# button_brightness_esp32.net
KiCad netlist of a schematic drawn in Altium Designer
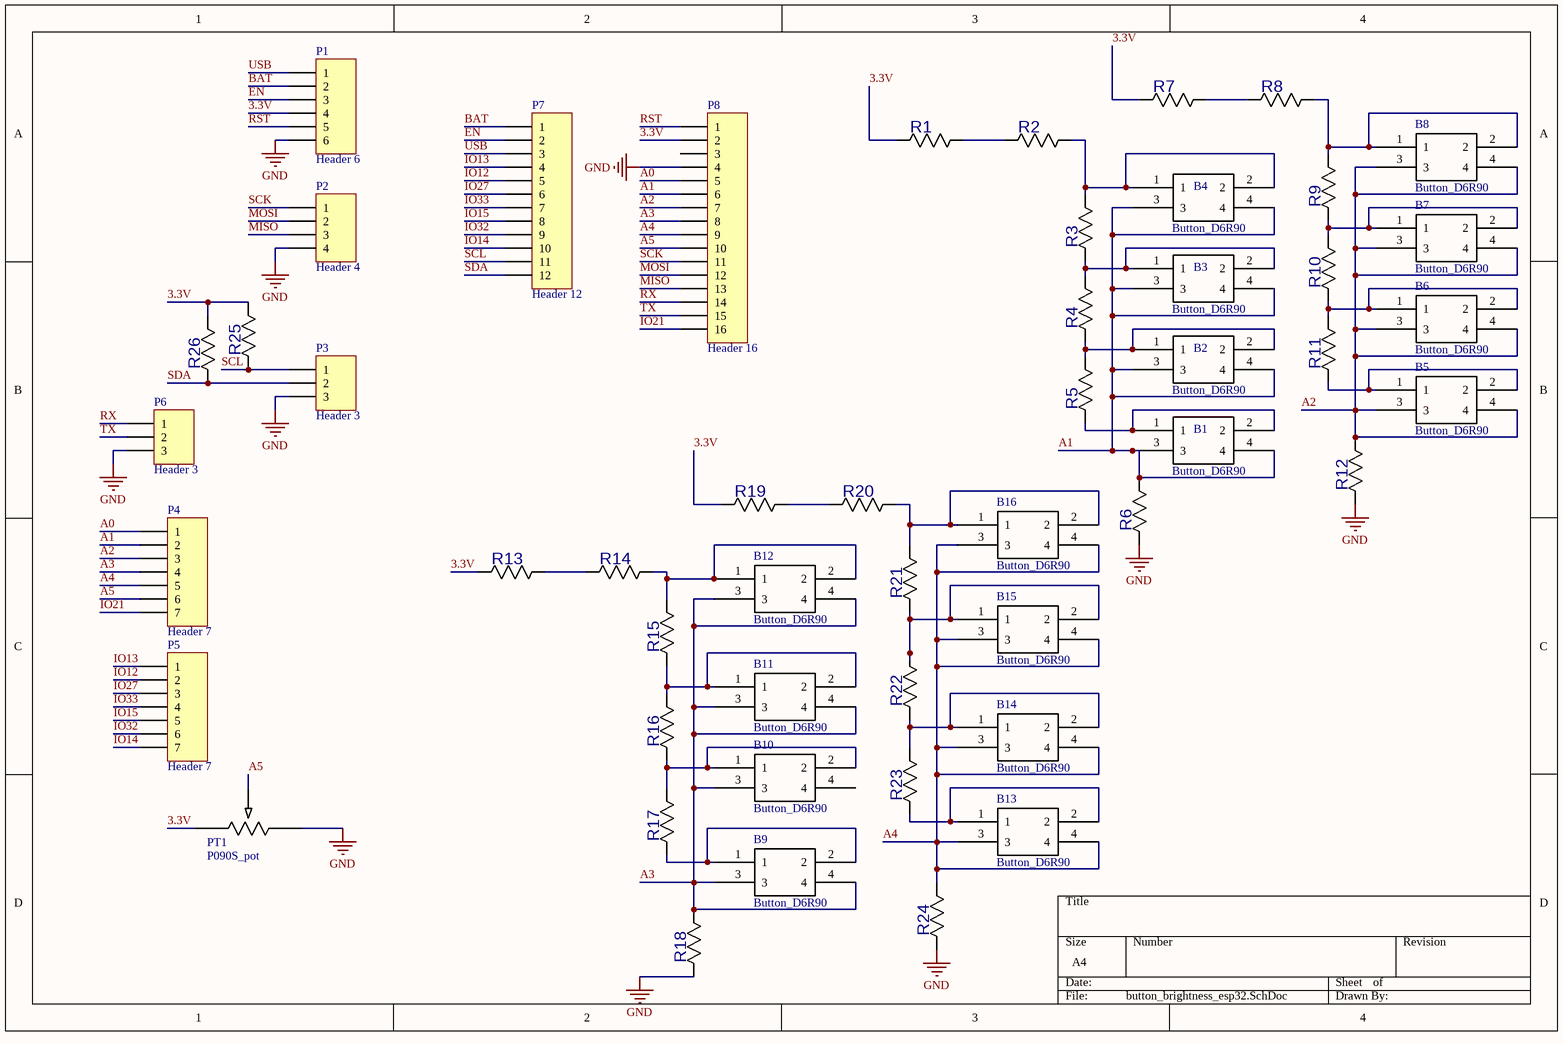
[diagram p0: button_brightness_esp32.SchDoc]

(export (version "E")
  (design (tool "Eeschema 10.0.6"))
  (components
    (comp (ref "B1")
      (value "Button_D6R90")
      (footprint "Button_D6R90")
      (libsource (lib "shematic_lib") (part "Button_D6R90"))
    )
    (comp (ref "B2")
      (value "Button_D6R90")
      (footprint "Button_D6R90")
      (libsource (lib "shematic_lib") (part "Button_D6R90"))
    )
    (comp (ref "B3")
      (value "Button_D6R90")
      (footprint "Button_D6R90")
      (libsource (lib "shematic_lib") (part "Button_D6R90"))
    )
    (comp (ref "B4")
      (value "Button_D6R90")
      (footprint "Button_D6R90")
      (libsource (lib "shematic_lib") (part "Button_D6R90"))
    )
    (comp (ref "B5")
      (value "Button_D6R90")
      (footprint "Button_D6R90")
      (libsource (lib "shematic_lib") (part "Button_D6R90"))
    )
    (comp (ref "B6")
      (value "Button_D6R90")
      (footprint "Button_D6R90")
      (libsource (lib "shematic_lib") (part "Button_D6R90"))
    )
    (comp (ref "B7")
      (value "Button_D6R90")
      (footprint "Button_D6R90")
      (libsource (lib "shematic_lib") (part "Button_D6R90"))
    )
    (comp (ref "B8")
      (value "Button_D6R90")
      (footprint "Button_D6R90")
      (libsource (lib "shematic_lib") (part "Button_D6R90"))
    )
    (comp (ref "B9")
      (value "Button_D6R90")
      (footprint "Button_D6R90")
      (libsource (lib "shematic_lib") (part "Button_D6R90"))
    )
    (comp (ref "B10")
      (value "Button_D6R90")
      (footprint "Button_D6R90")
      (libsource (lib "shematic_lib") (part "Button_D6R90"))
    )
    (comp (ref "B11")
      (value "Button_D6R90")
      (footprint "Button_D6R90")
      (libsource (lib "shematic_lib") (part "Button_D6R90"))
    )
    (comp (ref "B12")
      (value "Button_D6R90")
      (footprint "component_lib:Button_D6R90")
      (libsource (lib "shematic_lib") (part "Button_D6R90"))
    )
    (comp (ref "B13")
      (value "Button_D6R90")
      (footprint "Button_D6R90")
      (libsource (lib "shematic_lib") (part "Button_D6R90"))
    )
    (comp (ref "B14")
      (value "Button_D6R90")
      (footprint "Button_D6R90")
      (libsource (lib "shematic_lib") (part "Button_D6R90"))
    )
    (comp (ref "B15")
      (value "Button_D6R90")
      (footprint "Button_D6R90")
      (libsource (lib "shematic_lib") (part "Button_D6R90"))
    )
    (comp (ref "B16")
      (value "Button_D6R90")
      (footprint "Button_D6R90")
      (libsource (lib "shematic_lib") (part "Button_D6R90"))
    )
    (comp (ref "P1")
      (value "Header 6")
      (footprint "CONN_6")
      (description "Header, 6-Pin")
      (fields (field (name "PUBLISHER") "Altium Limited"))
      (libsource (lib "Miscellaneous Connectors") (part "Header 6"))
    )
    (comp (ref "P2")
      (value "Header 4")
      (footprint "CONN_4")
      (description "Header, 4-Pin")
      (fields (field (name "PUBLISHER") "Altium Limited"))
      (libsource (lib "Miscellaneous Connectors") (part "Header 4"))
    )
    (comp (ref "P3")
      (value "Header 3")
      (footprint "CONN_3")
      (description "Header, 3-Pin")
      (fields (field (name "PUBLISHER") "Altium Limited"))
      (libsource (lib "Miscellaneous Connectors") (part "Header 3"))
    )
    (comp (ref "P4")
      (value "Header 7")
      (footprint "CONN_7")
      (description "Header, 7-Pin")
      (fields (field (name "PUBLISHER") "Altium Limited"))
      (libsource (lib "Miscellaneous Connectors") (part "Header 7"))
    )
    (comp (ref "P5")
      (value "Header 7")
      (footprint "CONN_7")
      (description "Header, 7-Pin")
      (fields (field (name "PUBLISHER") "Altium Limited"))
      (libsource (lib "Miscellaneous Connectors") (part "Header 7"))
    )
    (comp (ref "P6")
      (value "Header 3")
      (footprint "CONN_3")
      (description "Header, 3-Pin")
      (fields (field (name "PUBLISHER") "Altium Limited"))
      (libsource (lib "Miscellaneous Connectors") (part "Header 3"))
    )
    (comp (ref "P7")
      (value "Header 12")
      (footprint "ESP32_feather_short_pins")
      (description "Header, 12-Pin")
      (fields (field (name "PUBLISHER") "Altium Limited"))
      (libsource (lib "Miscellaneous Connectors") (part "Header 12"))
    )
    (comp (ref "P8")
      (value "Header 16")
      (footprint "ESP32_feather_long_pins")
      (description "Header, 16-Pin")
      (fields (field (name "PUBLISHER") "Altium Limited"))
      (libsource (lib "Miscellaneous Connectors") (part "Header 16"))
    )
    (comp (ref "PT1")
      (value "P090S_pot")
      (footprint "P090S_pot")
      (libsource (lib "shematic_lib") (part "P090S_pot"))
    )
    (comp (ref "R1")
      (value "ERJ-6GEYJ471V")
      (footprint "component_lib:RES_0804_panasonic")
      (libsource (lib "shematic_lib") (part "ERJ-6GEYJ471V"))
    )
    (comp (ref "R2")
      (value "ERJ-6GEYJ471V")
      (footprint "component_lib:RES_0804_panasonic")
      (libsource (lib "shematic_lib") (part "ERJ-6GEYJ471V"))
    )
    (comp (ref "R3")
      (value "ERJ-6GEYJ471V")
      (footprint "component_lib:RES_0804_panasonic")
      (libsource (lib "shematic_lib") (part "ERJ-6GEYJ471V"))
    )
    (comp (ref "R4")
      (value "ERJ-6GEYJ471V")
      (footprint "component_lib:RES_0804_panasonic")
      (libsource (lib "shematic_lib") (part "ERJ-6GEYJ471V"))
    )
    (comp (ref "R5")
      (value "ERJ-6GEYJ471V")
      (footprint "component_lib:RES_0804_panasonic")
      (libsource (lib "shematic_lib") (part "ERJ-6GEYJ471V"))
    )
    (comp (ref "R6")
      (value "ERJ-6GEYJ471V")
      (footprint "component_lib:RES_0804_panasonic")
      (libsource (lib "shematic_lib") (part "ERJ-6GEYJ471V"))
    )
    (comp (ref "R7")
      (value "ERJ-6GEYJ471V")
      (footprint "component_lib:RES_0804_panasonic")
      (libsource (lib "shematic_lib") (part "ERJ-6GEYJ471V"))
    )
    (comp (ref "R8")
      (value "ERJ-6GEYJ471V")
      (footprint "component_lib:RES_0804_panasonic")
      (libsource (lib "shematic_lib") (part "ERJ-6GEYJ471V"))
    )
    (comp (ref "R9")
      (value "ERJ-6GEYJ471V")
      (footprint "component_lib:RES_0804_panasonic")
      (libsource (lib "shematic_lib") (part "ERJ-6GEYJ471V"))
    )
    (comp (ref "R10")
      (value "ERJ-6GEYJ471V")
      (footprint "component_lib:RES_0804_panasonic")
      (libsource (lib "shematic_lib") (part "ERJ-6GEYJ471V"))
    )
    (comp (ref "R11")
      (value "ERJ-6GEYJ471V")
      (footprint "component_lib:RES_0804_panasonic")
      (libsource (lib "shematic_lib") (part "ERJ-6GEYJ471V"))
    )
    (comp (ref "R12")
      (value "ERJ-6GEYJ471V")
      (footprint "component_lib:RES_0804_panasonic")
      (libsource (lib "shematic_lib") (part "ERJ-6GEYJ471V"))
    )
    (comp (ref "R13")
      (value "ERJ-6GEYJ471V")
      (footprint "component_lib:RES_0804_panasonic")
      (libsource (lib "shematic_lib") (part "ERJ-6GEYJ471V"))
    )
    (comp (ref "R14")
      (value "ERJ-6GEYJ471V")
      (footprint "component_lib:RES_0804_panasonic")
      (libsource (lib "shematic_lib") (part "ERJ-6GEYJ471V"))
    )
    (comp (ref "R15")
      (value "ERJ-6GEYJ471V")
      (footprint "component_lib:RES_0804_panasonic")
      (libsource (lib "shematic_lib") (part "ERJ-6GEYJ471V"))
    )
    (comp (ref "R16")
      (value "ERJ-6GEYJ471V")
      (footprint "component_lib:RES_0804_panasonic")
      (libsource (lib "shematic_lib") (part "ERJ-6GEYJ471V"))
    )
    (comp (ref "R17")
      (value "ERJ-6GEYJ471V")
      (footprint "component_lib:RES_0804_panasonic")
      (libsource (lib "shematic_lib") (part "ERJ-6GEYJ471V"))
    )
    (comp (ref "R18")
      (value "ERJ-6GEYJ471V")
      (footprint "component_lib:RES_0804_panasonic")
      (libsource (lib "shematic_lib") (part "ERJ-6GEYJ471V"))
    )
    (comp (ref "R19")
      (value "ERJ-6GEYJ471V")
      (footprint "component_lib:RES_0804_panasonic")
      (libsource (lib "shematic_lib") (part "ERJ-6GEYJ471V"))
    )
    (comp (ref "R20")
      (value "ERJ-6GEYJ471V")
      (footprint "component_lib:RES_0804_panasonic")
      (libsource (lib "shematic_lib") (part "ERJ-6GEYJ471V"))
    )
    (comp (ref "R21")
      (value "ERJ-6GEYJ471V")
      (footprint "component_lib:RES_0804_panasonic")
      (libsource (lib "shematic_lib") (part "ERJ-6GEYJ471V"))
    )
    (comp (ref "R22")
      (value "ERJ-6GEYJ471V")
      (footprint "component_lib:RES_0804_panasonic")
      (libsource (lib "shematic_lib") (part "ERJ-6GEYJ471V"))
    )
    (comp (ref "R23")
      (value "ERJ-6GEYJ471V")
      (footprint "component_lib:RES_0804_panasonic")
      (libsource (lib "shematic_lib") (part "ERJ-6GEYJ471V"))
    )
    (comp (ref "R24")
      (value "ERJ-6GEYJ471V")
      (footprint "component_lib:RES_0804_panasonic")
      (libsource (lib "shematic_lib") (part "ERJ-6GEYJ471V"))
    )
    (comp (ref "R25")
      (value "ERJ-6GEYJ471V")
      (footprint "component_lib:RES_0804_panasonic")
      (libsource (lib "shematic_lib") (part "ERJ-6GEYJ471V"))
    )
    (comp (ref "R26")
      (value "ERJ-6GEYJ471V")
      (footprint "component_lib:RES_0804_panasonic")
      (libsource (lib "shematic_lib") (part "ERJ-6GEYJ471V"))
    )
  )
  (nets
    (net (code "1") (name "/3.3V") (class "Default")
      (node (ref "P1") (pin "4") (pinfunction "4_4") (pintype "passive"))
      (node (ref "P8") (pin "2") (pinfunction "2_2") (pintype "passive"))
      (node (ref "PT1") (pin "1") (pinfunction "1_1") (pintype "passive"))
      (node (ref "R1") (pin "2") (pinfunction "2_2") (pintype "passive"))
      (node (ref "R13") (pin "2") (pinfunction "2_2") (pintype "passive"))
      (node (ref "R19") (pin "2") (pinfunction "2_2") (pintype "passive"))
      (node (ref "R25") (pin "1") (pinfunction "1_1") (pintype "passive"))
      (node (ref "R26") (pin "1") (pinfunction "1_1") (pintype "passive"))
      (node (ref "R7") (pin "2") (pinfunction "2_2") (pintype "passive"))
    )
    (net (code "2") (name "/A0") (class "Default")
      (node (ref "P4") (pin "1") (pinfunction "1_1") (pintype "passive"))
      (node (ref "P8") (pin "5") (pinfunction "5_5") (pintype "passive"))
    )
    (net (code "3") (name "/A1") (class "Default")
      (node (ref "B1") (pin "3") (pinfunction "3_3") (pintype "passive"))
      (node (ref "B1") (pin "4") (pinfunction "4_4") (pintype "passive"))
      (node (ref "B2") (pin "3") (pinfunction "3_3") (pintype "passive"))
      (node (ref "B2") (pin "4") (pinfunction "4_4") (pintype "passive"))
      (node (ref "B3") (pin "3") (pinfunction "3_3") (pintype "passive"))
      (node (ref "B3") (pin "4") (pinfunction "4_4") (pintype "passive"))
      (node (ref "B4") (pin "3") (pinfunction "3_3") (pintype "passive"))
      (node (ref "B4") (pin "4") (pinfunction "4_4") (pintype "passive"))
      (node (ref "P4") (pin "2") (pinfunction "2_2") (pintype "passive"))
      (node (ref "P8") (pin "6") (pinfunction "6_6") (pintype "passive"))
      (node (ref "R6") (pin "1") (pinfunction "1_1") (pintype "passive"))
    )
    (net (code "4") (name "/A2") (class "Default")
      (node (ref "B5") (pin "3") (pinfunction "3_3") (pintype "passive"))
      (node (ref "B5") (pin "4") (pinfunction "4_4") (pintype "passive"))
      (node (ref "B6") (pin "3") (pinfunction "3_3") (pintype "passive"))
      (node (ref "B6") (pin "4") (pinfunction "4_4") (pintype "passive"))
      (node (ref "B7") (pin "3") (pinfunction "3_3") (pintype "passive"))
      (node (ref "B7") (pin "4") (pinfunction "4_4") (pintype "passive"))
      (node (ref "B8") (pin "3") (pinfunction "3_3") (pintype "passive"))
      (node (ref "B8") (pin "4") (pinfunction "4_4") (pintype "passive"))
      (node (ref "P4") (pin "3") (pinfunction "3_3") (pintype "passive"))
      (node (ref "P8") (pin "7") (pinfunction "7_7") (pintype "passive"))
      (node (ref "R12") (pin "1") (pinfunction "1_1") (pintype "passive"))
    )
    (net (code "5") (name "/A3") (class "Default")
      (node (ref "B10") (pin "3") (pinfunction "3_3") (pintype "passive"))
      (node (ref "B11") (pin "3") (pinfunction "3_3") (pintype "passive"))
      (node (ref "B11") (pin "4") (pinfunction "4_4") (pintype "passive"))
      (node (ref "B12") (pin "3") (pinfunction "3_3") (pintype "passive"))
      (node (ref "B12") (pin "4") (pinfunction "4_4") (pintype "passive"))
      (node (ref "B9") (pin "3") (pinfunction "3_3") (pintype "passive"))
      (node (ref "B9") (pin "4") (pinfunction "4_4") (pintype "passive"))
      (node (ref "P4") (pin "4") (pinfunction "4_4") (pintype "passive"))
      (node (ref "P8") (pin "8") (pinfunction "8_8") (pintype "passive"))
      (node (ref "R18") (pin "1") (pinfunction "1_1") (pintype "passive"))
    )
    (net (code "6") (name "/A4") (class "Default")
      (node (ref "B13") (pin "3") (pinfunction "3_3") (pintype "passive"))
      (node (ref "B13") (pin "4") (pinfunction "4_4") (pintype "passive"))
      (node (ref "B14") (pin "3") (pinfunction "3_3") (pintype "passive"))
      (node (ref "B14") (pin "4") (pinfunction "4_4") (pintype "passive"))
      (node (ref "B15") (pin "3") (pinfunction "3_3") (pintype "passive"))
      (node (ref "B15") (pin "4") (pinfunction "4_4") (pintype "passive"))
      (node (ref "B16") (pin "3") (pinfunction "3_3") (pintype "passive"))
      (node (ref "B16") (pin "4") (pinfunction "4_4") (pintype "passive"))
      (node (ref "P4") (pin "5") (pinfunction "5_5") (pintype "passive"))
      (node (ref "P8") (pin "9") (pinfunction "9_9") (pintype "passive"))
      (node (ref "R24") (pin "1") (pinfunction "1_1") (pintype "passive"))
    )
    (net (code "7") (name "/A5") (class "Default")
      (node (ref "P4") (pin "6") (pinfunction "6_6") (pintype "passive"))
      (node (ref "P8") (pin "10") (pinfunction "10_10") (pintype "passive"))
      (node (ref "PT1") (pin "2") (pinfunction "2_2") (pintype "passive"))
    )
    (net (code "8") (name "/BAT") (class "Default")
      (node (ref "P1") (pin "2") (pinfunction "2_2") (pintype "passive"))
      (node (ref "P7") (pin "1") (pinfunction "1_1") (pintype "passive"))
    )
    (net (code "9") (name "/EN") (class "Default")
      (node (ref "P1") (pin "3") (pinfunction "3_3") (pintype "passive"))
      (node (ref "P7") (pin "2") (pinfunction "2_2") (pintype "passive"))
    )
    (net (code "10") (name "/IO12") (class "Default")
      (node (ref "P5") (pin "2") (pinfunction "2_2") (pintype "passive"))
      (node (ref "P7") (pin "5") (pinfunction "5_5") (pintype "passive"))
    )
    (net (code "11") (name "/IO13") (class "Default")
      (node (ref "P5") (pin "1") (pinfunction "1_1") (pintype "passive"))
      (node (ref "P7") (pin "4") (pinfunction "4_4") (pintype "passive"))
    )
    (net (code "12") (name "/IO14") (class "Default")
      (node (ref "P5") (pin "7") (pinfunction "7_7") (pintype "passive"))
      (node (ref "P7") (pin "10") (pinfunction "10_10") (pintype "passive"))
    )
    (net (code "13") (name "/IO15") (class "Default")
      (node (ref "P5") (pin "5") (pinfunction "5_5") (pintype "passive"))
      (node (ref "P7") (pin "8") (pinfunction "8_8") (pintype "passive"))
    )
    (net (code "14") (name "/IO21") (class "Default")
      (node (ref "P4") (pin "7") (pinfunction "7_7") (pintype "passive"))
      (node (ref "P8") (pin "16") (pinfunction "16_16") (pintype "passive"))
    )
    (net (code "15") (name "/IO27") (class "Default")
      (node (ref "P5") (pin "3") (pinfunction "3_3") (pintype "passive"))
      (node (ref "P7") (pin "6") (pinfunction "6_6") (pintype "passive"))
    )
    (net (code "16") (name "/IO32") (class "Default")
      (node (ref "P5") (pin "6") (pinfunction "6_6") (pintype "passive"))
      (node (ref "P7") (pin "9") (pinfunction "9_9") (pintype "passive"))
    )
    (net (code "17") (name "/IO33") (class "Default")
      (node (ref "P5") (pin "4") (pinfunction "4_4") (pintype "passive"))
      (node (ref "P7") (pin "7") (pinfunction "7_7") (pintype "passive"))
    )
    (net (code "18") (name "/MISO") (class "Default")
      (node (ref "P2") (pin "3") (pinfunction "3_3") (pintype "passive"))
      (node (ref "P8") (pin "13") (pinfunction "13_13") (pintype "passive"))
    )
    (net (code "19") (name "/MOSI") (class "Default")
      (node (ref "P2") (pin "2") (pinfunction "2_2") (pintype "passive"))
      (node (ref "P8") (pin "12") (pinfunction "12_12") (pintype "passive"))
    )
    (net (code "20") (name "/RST") (class "Default")
      (node (ref "P1") (pin "5") (pinfunction "5_5") (pintype "passive"))
      (node (ref "P8") (pin "1") (pinfunction "1_1") (pintype "passive"))
    )
    (net (code "21") (name "/RX") (class "Default")
      (node (ref "P6") (pin "1") (pinfunction "1_1") (pintype "passive"))
      (node (ref "P8") (pin "14") (pinfunction "14_14") (pintype "passive"))
    )
    (net (code "22") (name "/SCK") (class "Default")
      (node (ref "P2") (pin "1") (pinfunction "1_1") (pintype "passive"))
      (node (ref "P8") (pin "11") (pinfunction "11_11") (pintype "passive"))
    )
    (net (code "23") (name "/SCL") (class "Default")
      (node (ref "P3") (pin "1") (pinfunction "1_1") (pintype "passive"))
      (node (ref "P7") (pin "11") (pinfunction "11_11") (pintype "passive"))
      (node (ref "R25") (pin "2") (pinfunction "2_2") (pintype "passive"))
    )
    (net (code "24") (name "/SDA") (class "Default")
      (node (ref "P3") (pin "2") (pinfunction "2_2") (pintype "passive"))
      (node (ref "P7") (pin "12") (pinfunction "12_12") (pintype "passive"))
      (node (ref "R26") (pin "2") (pinfunction "2_2") (pintype "passive"))
    )
    (net (code "25") (name "/TX") (class "Default")
      (node (ref "P6") (pin "2") (pinfunction "2_2") (pintype "passive"))
      (node (ref "P8") (pin "15") (pinfunction "15_15") (pintype "passive"))
    )
    (net (code "26") (name "/USB") (class "Default")
      (node (ref "P1") (pin "1") (pinfunction "1_1") (pintype "passive"))
      (node (ref "P7") (pin "3") (pinfunction "3_3") (pintype "passive"))
    )
    (net (code "27") (name "GND") (class "Default")
      (node (ref "P1") (pin "6") (pinfunction "6_6") (pintype "passive"))
      (node (ref "P2") (pin "4") (pinfunction "4_4") (pintype "passive"))
      (node (ref "P3") (pin "3") (pinfunction "3_3") (pintype "passive"))
      (node (ref "P6") (pin "3") (pinfunction "3_3") (pintype "passive"))
      (node (ref "P8") (pin "4") (pinfunction "4_4") (pintype "passive"))
      (node (ref "PT1") (pin "3") (pinfunction "3_3") (pintype "passive"))
      (node (ref "R12") (pin "2") (pinfunction "2_2") (pintype "passive"))
      (node (ref "R18") (pin "2") (pinfunction "2_2") (pintype "passive"))
      (node (ref "R24") (pin "2") (pinfunction "2_2") (pintype "passive"))
      (node (ref "R6") (pin "2") (pinfunction "2_2") (pintype "passive"))
    )
    (net (code "28") (name "Net-(B1-Pad1)") (class "Default")
      (node (ref "B1") (pin "1") (pinfunction "1_1") (pintype "passive"))
      (node (ref "B1") (pin "2") (pinfunction "2_2") (pintype "passive"))
      (node (ref "R5") (pin "2") (pinfunction "2_2") (pintype "passive"))
    )
    (net (code "29") (name "Net-(B2-Pad1)") (class "Default")
      (node (ref "B2") (pin "1") (pinfunction "1_1") (pintype "passive"))
      (node (ref "B2") (pin "2") (pinfunction "2_2") (pintype "passive"))
      (node (ref "R4") (pin "2") (pinfunction "2_2") (pintype "passive"))
      (node (ref "R5") (pin "1") (pinfunction "1_1") (pintype "passive"))
    )
    (net (code "30") (name "Net-(B3-Pad1)") (class "Default")
      (node (ref "B3") (pin "1") (pinfunction "1_1") (pintype "passive"))
      (node (ref "B3") (pin "2") (pinfunction "2_2") (pintype "passive"))
      (node (ref "R3") (pin "2") (pinfunction "2_2") (pintype "passive"))
      (node (ref "R4") (pin "1") (pinfunction "1_1") (pintype "passive"))
    )
    (net (code "31") (name "Net-(B4-Pad1)") (class "Default")
      (node (ref "B4") (pin "1") (pinfunction "1_1") (pintype "passive"))
      (node (ref "B4") (pin "2") (pinfunction "2_2") (pintype "passive"))
      (node (ref "R2") (pin "1") (pinfunction "1_1") (pintype "passive"))
      (node (ref "R3") (pin "1") (pinfunction "1_1") (pintype "passive"))
    )
    (net (code "32") (name "Net-(B5-Pad1)") (class "Default")
      (node (ref "B5") (pin "1") (pinfunction "1_1") (pintype "passive"))
      (node (ref "B5") (pin "2") (pinfunction "2_2") (pintype "passive"))
      (node (ref "R11") (pin "2") (pinfunction "2_2") (pintype "passive"))
    )
    (net (code "33") (name "Net-(B6-Pad1)") (class "Default")
      (node (ref "B6") (pin "1") (pinfunction "1_1") (pintype "passive"))
      (node (ref "B6") (pin "2") (pinfunction "2_2") (pintype "passive"))
      (node (ref "R10") (pin "2") (pinfunction "2_2") (pintype "passive"))
      (node (ref "R11") (pin "1") (pinfunction "1_1") (pintype "passive"))
    )
    (net (code "34") (name "Net-(B7-Pad1)") (class "Default")
      (node (ref "B7") (pin "1") (pinfunction "1_1") (pintype "passive"))
      (node (ref "B7") (pin "2") (pinfunction "2_2") (pintype "passive"))
      (node (ref "R10") (pin "1") (pinfunction "1_1") (pintype "passive"))
      (node (ref "R9") (pin "2") (pinfunction "2_2") (pintype "passive"))
    )
    (net (code "35") (name "Net-(B8-Pad1)") (class "Default")
      (node (ref "B8") (pin "1") (pinfunction "1_1") (pintype "passive"))
      (node (ref "B8") (pin "2") (pinfunction "2_2") (pintype "passive"))
      (node (ref "R8") (pin "1") (pinfunction "1_1") (pintype "passive"))
      (node (ref "R9") (pin "1") (pinfunction "1_1") (pintype "passive"))
    )
    (net (code "36") (name "Net-(B9-Pad1)") (class "Default")
      (node (ref "B9") (pin "1") (pinfunction "1_1") (pintype "passive"))
      (node (ref "B9") (pin "2") (pinfunction "2_2") (pintype "passive"))
      (node (ref "R17") (pin "2") (pinfunction "2_2") (pintype "passive"))
    )
    (net (code "37") (name "Net-(B10-Pad1)") (class "Default")
      (node (ref "B10") (pin "1") (pinfunction "1_1") (pintype "passive"))
      (node (ref "B10") (pin "2") (pinfunction "2_2") (pintype "passive"))
      (node (ref "R16") (pin "2") (pinfunction "2_2") (pintype "passive"))
      (node (ref "R17") (pin "1") (pinfunction "1_1") (pintype "passive"))
    )
    (net (code "38") (name "Net-(B11-Pad1)") (class "Default")
      (node (ref "B11") (pin "1") (pinfunction "1_1") (pintype "passive"))
      (node (ref "B11") (pin "2") (pinfunction "2_2") (pintype "passive"))
      (node (ref "R15") (pin "2") (pinfunction "2_2") (pintype "passive"))
      (node (ref "R16") (pin "1") (pinfunction "1_1") (pintype "passive"))
    )
    (net (code "39") (name "Net-(B12-Pad1)") (class "Default")
      (node (ref "B12") (pin "1") (pinfunction "1_1") (pintype "passive"))
      (node (ref "B12") (pin "2") (pinfunction "2_2") (pintype "passive"))
      (node (ref "R14") (pin "1") (pinfunction "1_1") (pintype "passive"))
      (node (ref "R15") (pin "1") (pinfunction "1_1") (pintype "passive"))
    )
    (net (code "40") (name "Net-(B13-Pad1)") (class "Default")
      (node (ref "B13") (pin "1") (pinfunction "1_1") (pintype "passive"))
      (node (ref "B13") (pin "2") (pinfunction "2_2") (pintype "passive"))
      (node (ref "R23") (pin "2") (pinfunction "2_2") (pintype "passive"))
    )
    (net (code "41") (name "Net-(B14-Pad1)") (class "Default")
      (node (ref "B14") (pin "1") (pinfunction "1_1") (pintype "passive"))
      (node (ref "B14") (pin "2") (pinfunction "2_2") (pintype "passive"))
      (node (ref "R22") (pin "2") (pinfunction "2_2") (pintype "passive"))
      (node (ref "R23") (pin "1") (pinfunction "1_1") (pintype "passive"))
    )
    (net (code "42") (name "Net-(B15-Pad1)") (class "Default")
      (node (ref "B15") (pin "1") (pinfunction "1_1") (pintype "passive"))
      (node (ref "B15") (pin "2") (pinfunction "2_2") (pintype "passive"))
      (node (ref "R21") (pin "2") (pinfunction "2_2") (pintype "passive"))
      (node (ref "R22") (pin "1") (pinfunction "1_1") (pintype "passive"))
    )
    (net (code "43") (name "Net-(B16-Pad1)") (class "Default")
      (node (ref "B16") (pin "1") (pinfunction "1_1") (pintype "passive"))
      (node (ref "B16") (pin "2") (pinfunction "2_2") (pintype "passive"))
      (node (ref "R20") (pin "1") (pinfunction "1_1") (pintype "passive"))
      (node (ref "R21") (pin "1") (pinfunction "1_1") (pintype "passive"))
    )
    (net (code "44") (name "Net-(R1-Pad1)") (class "Default")
      (node (ref "R1") (pin "1") (pinfunction "1_1") (pintype "passive"))
      (node (ref "R2") (pin "2") (pinfunction "2_2") (pintype "passive"))
    )
    (net (code "45") (name "Net-(R7-Pad1)") (class "Default")
      (node (ref "R7") (pin "1") (pinfunction "1_1") (pintype "passive"))
      (node (ref "R8") (pin "2") (pinfunction "2_2") (pintype "passive"))
    )
    (net (code "46") (name "Net-(R13-Pad1)") (class "Default")
      (node (ref "R13") (pin "1") (pinfunction "1_1") (pintype "passive"))
      (node (ref "R14") (pin "2") (pinfunction "2_2") (pintype "passive"))
    )
    (net (code "47") (name "Net-(R19-Pad1)") (class "Default")
      (node (ref "R19") (pin "1") (pinfunction "1_1") (pintype "passive"))
      (node (ref "R20") (pin "2") (pinfunction "2_2") (pintype "passive"))
    )
    (net (code "48") (name "unconnected-(B10-Pad4)") (class "Default")
      (node (ref "B10") (pin "4") (pinfunction "4_4") (pintype "passive"))
    )
    (net (code "49") (name "unconnected-(P8-Pad3)") (class "Default")
      (node (ref "P8") (pin "3") (pinfunction "3_3") (pintype "passive"))
    )
  )
)
